# mrna_badge_v1_3.net
KiCad netlist of a schematic drawn in EAGLE
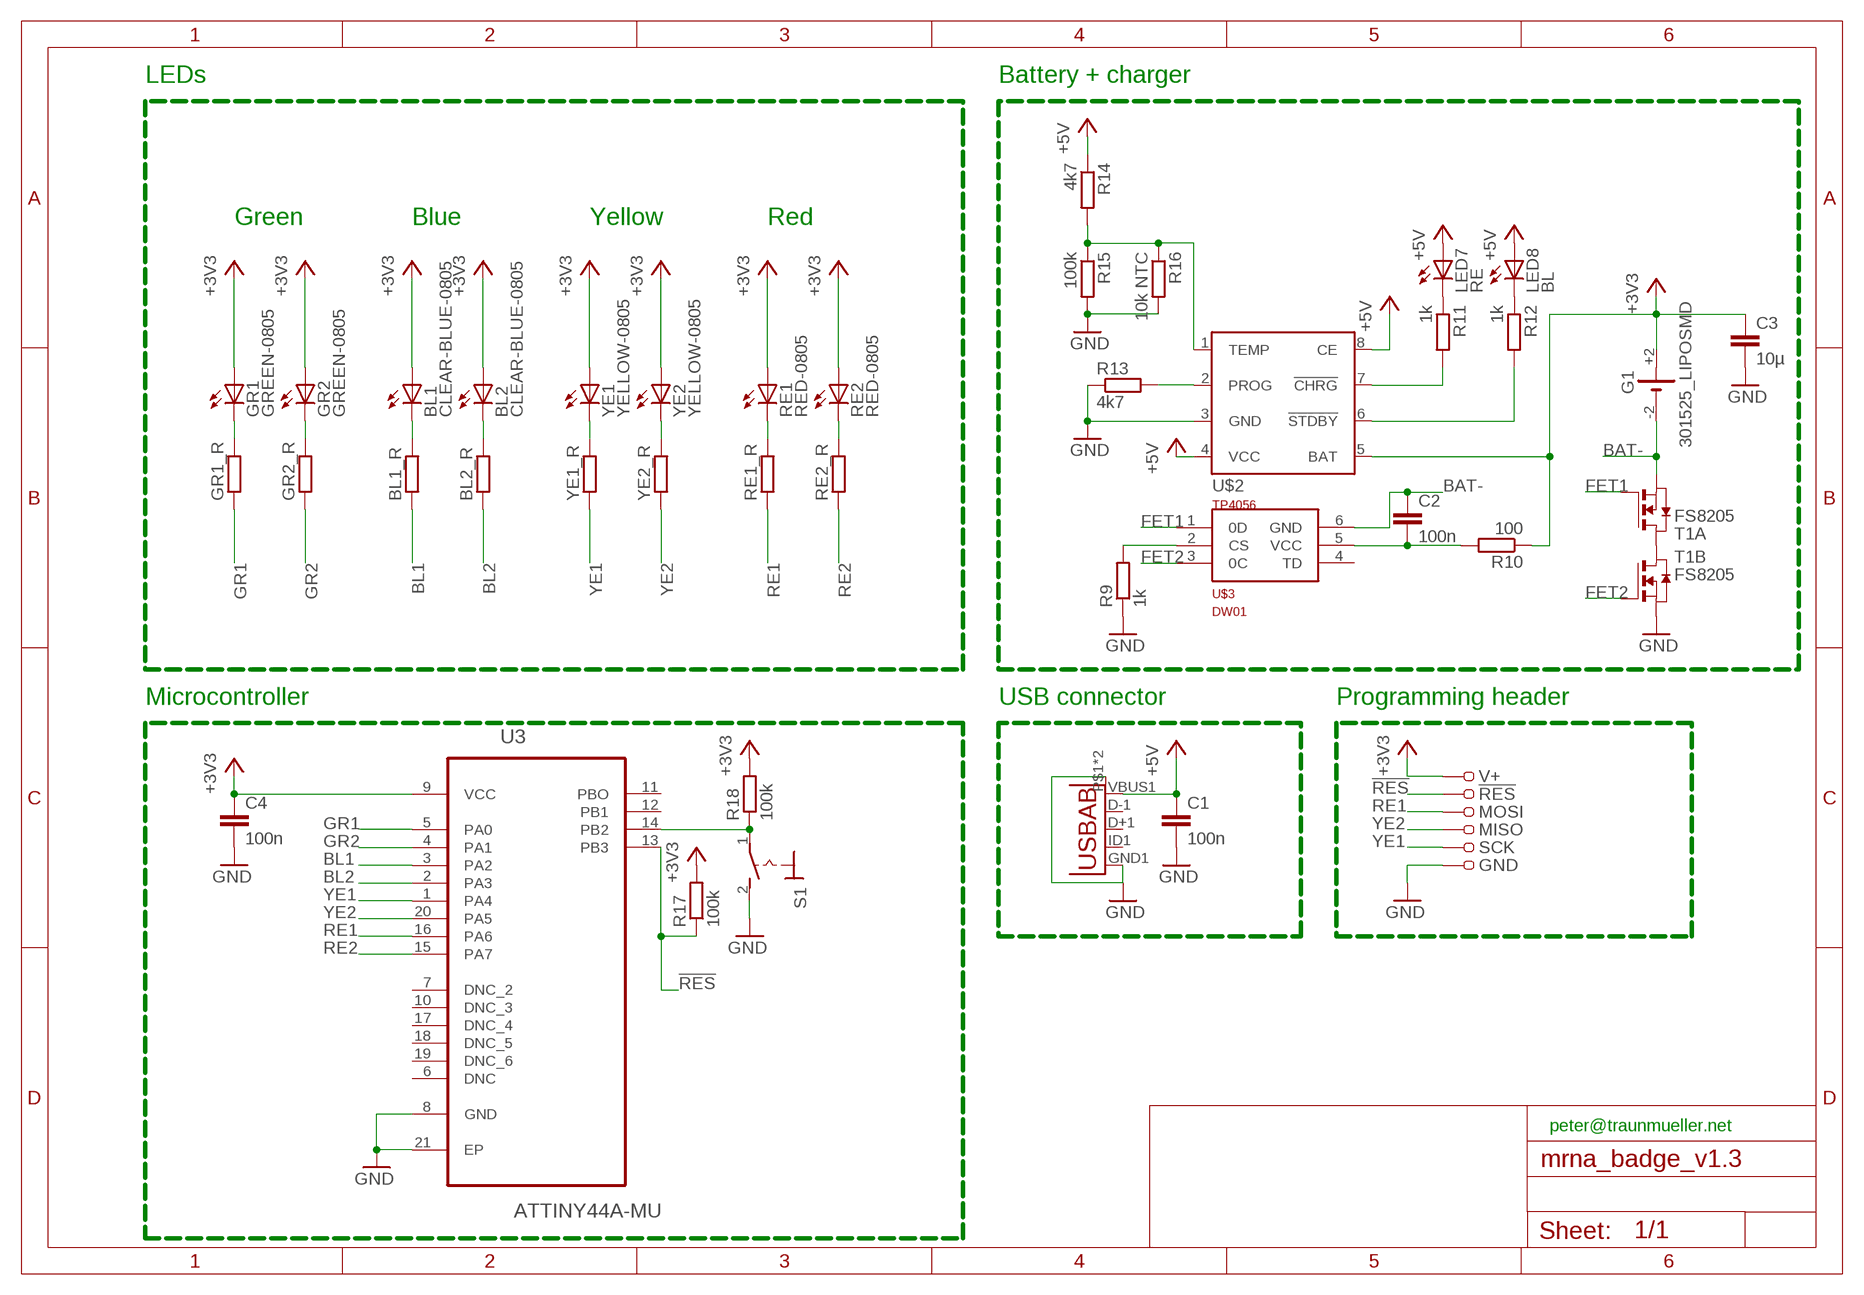
[diagram p0: schematic, sheet 1]

(export (version "E")
  (design (tool "Eeschema 10.0.6"))
  (components
    (comp (ref "!RES")
      (value "0.7MM_POGO-PINSPADS")
      (footprint "eagle-import:0.7MM_SMD_PADS")
      (libsource (lib "eagle-import") (part "0.7MM_POGO-PINSPADS"))
    )
    (comp (ref "BL1")
      (value "CLEAR-BLUE-0805")
      (footprint "eagle-import:CHIPLED_0805")
      (libsource (lib "eagle-import") (part "LEDCHIPLED_0805"))
    )
    (comp (ref "BL1_R")
      (value "R-EU_R0402")
      (footprint "eagle-import:R0402")
      (libsource (lib "eagle-import") (part "R-EU_R0402"))
    )
    (comp (ref "BL2")
      (value "CLEAR-BLUE-0805")
      (footprint "eagle-import:CHIPLED_0805")
      (libsource (lib "eagle-import") (part "LEDCHIPLED_0805"))
    )
    (comp (ref "BL2_R")
      (value "R-EU_R0402")
      (footprint "eagle-import:R0402")
      (libsource (lib "eagle-import") (part "R-EU_R0402"))
    )
    (comp (ref "C1")
      (value "100n")
      (footprint "eagle-import:C0402K")
      (libsource (lib "eagle-import") (part "C-EUC0402K"))
    )
    (comp (ref "C2")
      (value "100n")
      (footprint "eagle-import:C0402K")
      (libsource (lib "eagle-import") (part "C-EUC0402K"))
    )
    (comp (ref "C3")
      (value "10µ")
      (footprint "eagle-import:C0805K")
      (libsource (lib "eagle-import") (part "C-EUC0805K"))
    )
    (comp (ref "C4")
      (value "100n")
      (footprint "eagle-import:C0402K")
      (libsource (lib "eagle-import") (part "C-EUC0402K"))
    )
    (comp (ref "G1")
      (value "301525_LIPOSMD")
      (footprint "eagle-import:301525_LIPO_SMDCONTACTS")
      (libsource (lib "eagle-import") (part "301525_LIPOSMD"))
    )
    (comp (ref "GND")
      (value "0.7MM_POGO-PINSPADS")
      (footprint "eagle-import:0.7MM_SMD_PADS")
      (libsource (lib "eagle-import") (part "0.7MM_POGO-PINSPADS"))
    )
    (comp (ref "GR1")
      (value "GREEN-0805")
      (footprint "eagle-import:CHIPLED_0805")
      (libsource (lib "eagle-import") (part "LEDCHIPLED_0805"))
    )
    (comp (ref "GR1_R")
      (value "R-EU_R0402")
      (footprint "eagle-import:R0402")
      (libsource (lib "eagle-import") (part "R-EU_R0402"))
    )
    (comp (ref "GR2")
      (value "GREEN-0805")
      (footprint "eagle-import:CHIPLED_0805")
      (libsource (lib "eagle-import") (part "LEDCHIPLED_0805"))
    )
    (comp (ref "GR2_R")
      (value "R-EU_R0402")
      (footprint "eagle-import:R0402")
      (libsource (lib "eagle-import") (part "R-EU_R0402"))
    )
    (comp (ref "LED7")
      (value "RE")
      (footprint "eagle-import:CHIPLED_0603")
      (libsource (lib "eagle-import") (part "LEDCHIPLED_0603"))
    )
    (comp (ref "LED8")
      (value "BL")
      (footprint "eagle-import:CHIPLED_0603")
      (libsource (lib "eagle-import") (part "LEDCHIPLED_0603"))
    )
    (comp (ref "MISO")
      (value "0.7MM_POGO-PINSPADS")
      (footprint "eagle-import:0.7MM_SMD_PADS")
      (libsource (lib "eagle-import") (part "0.7MM_POGO-PINSPADS"))
    )
    (comp (ref "MOSI")
      (value "0.7MM_POGO-PINSPADS")
      (footprint "eagle-import:0.7MM_SMD_PADS")
      (libsource (lib "eagle-import") (part "0.7MM_POGO-PINSPADS"))
    )
    (comp (ref "R9")
      (value "1k")
      (footprint "eagle-import:R0402")
      (libsource (lib "eagle-import") (part "R-EU_R0402"))
    )
    (comp (ref "R10")
      (value "100")
      (footprint "eagle-import:R0402")
      (libsource (lib "eagle-import") (part "R-EU_R0402"))
    )
    (comp (ref "R11")
      (value "1k")
      (footprint "eagle-import:R0402")
      (libsource (lib "eagle-import") (part "R-EU_R0402"))
    )
    (comp (ref "R12")
      (value "1k")
      (footprint "eagle-import:R0402")
      (libsource (lib "eagle-import") (part "R-EU_R0402"))
    )
    (comp (ref "R13")
      (value "4k7")
      (footprint "eagle-import:R0402")
      (libsource (lib "eagle-import") (part "R-EU_R0402"))
    )
    (comp (ref "R14")
      (value "4k7")
      (footprint "eagle-import:R0402")
      (libsource (lib "eagle-import") (part "R-EU_R0402"))
    )
    (comp (ref "R15")
      (value "100k")
      (footprint "eagle-import:R0402")
      (libsource (lib "eagle-import") (part "R-EU_R0402"))
    )
    (comp (ref "R16")
      (value "10k NTC")
      (footprint "eagle-import:R0805")
      (libsource (lib "eagle-import") (part "R-EU_R0805"))
    )
    (comp (ref "R17")
      (value "100k")
      (footprint "eagle-import:R0402")
      (libsource (lib "eagle-import") (part "R-EU_R0402"))
    )
    (comp (ref "R18")
      (value "100k")
      (footprint "eagle-import:R0402")
      (libsource (lib "eagle-import") (part "R-EU_R0402"))
    )
    (comp (ref "RE1")
      (value "RED-0805")
      (footprint "eagle-import:CHIPLED_0805")
      (libsource (lib "eagle-import") (part "LEDCHIPLED_0805"))
    )
    (comp (ref "RE1_R")
      (value "R-EU_R0402")
      (footprint "eagle-import:R0402")
      (libsource (lib "eagle-import") (part "R-EU_R0402"))
    )
    (comp (ref "RE2")
      (value "RED-0805")
      (footprint "eagle-import:CHIPLED_0805")
      (libsource (lib "eagle-import") (part "LEDCHIPLED_0805"))
    )
    (comp (ref "RE2_R")
      (value "R-EU_R0402")
      (footprint "eagle-import:R0402")
      (libsource (lib "eagle-import") (part "R-EU_R0402"))
    )
    (comp (ref "S1")
      (value "TS-1088NOHOLES")
      (footprint "eagle-import:TS-1088_NOHOLES")
      (libsource (lib "eagle-import") (part "TS-1088NOHOLES"))
    )
    (comp (ref "SCK")
      (value "0.7MM_POGO-PINSPADS")
      (footprint "eagle-import:0.7MM_SMD_PADS")
      (libsource (lib "eagle-import") (part "0.7MM_POGO-PINSPADS"))
    )
    (comp (ref "T1")
      (value "FS8205")
      (footprint "eagle-import:TSSOP-8")
      (libsource (lib "eagle-import") (part "DMN3024LSD"))
    )
    (comp (ref "U$2")
      (value "TP4056ESOP")
      (footprint "eagle-import:ESOP23-8")
      (libsource (lib "eagle-import") (part "TP4056ESOP"))
    )
    (comp (ref "U$3")
      (value "DW01")
      (footprint "eagle-import:SOT23-6")
      (libsource (lib "eagle-import") (part "DW01"))
    )
    (comp (ref "U2")
      (value "USB\"\"")
      (footprint "eagle-import:USB-MICRO-SMD")
      (libsource (lib "eagle-import") (part "USB{dblquote}{dblquote}"))
    )
    (comp (ref "U3")
      (value "ATTINY44A-MU")
      (footprint "eagle-import:QFN50P400X400X80-21N_FOOTPRINT")
      (libsource (lib "eagle-import") (part "ATTINY24A-MUFOOT"))
    )
    (comp (ref "V+")
      (value "0.7MM_POGO-PINSPADS")
      (footprint "eagle-import:0.7MM_SMD_PADS")
      (libsource (lib "eagle-import") (part "0.7MM_POGO-PINSPADS"))
    )
    (comp (ref "YE1")
      (value "YELLOW-0805")
      (footprint "eagle-import:CHIPLED_0805")
      (libsource (lib "eagle-import") (part "LEDCHIPLED_0805"))
    )
    (comp (ref "YE1_R")
      (value "R-EU_R0402")
      (footprint "eagle-import:R0402")
      (libsource (lib "eagle-import") (part "R-EU_R0402"))
    )
    (comp (ref "YE2")
      (value "YELLOW-0805")
      (footprint "eagle-import:CHIPLED_0805")
      (libsource (lib "eagle-import") (part "LEDCHIPLED_0805"))
    )
    (comp (ref "YE2_R")
      (value "R-EU_R0402")
      (footprint "eagle-import:R0402")
      (libsource (lib "eagle-import") (part "R-EU_R0402"))
    )
  )
  (nets
    (net (code "1") (name "+3V3") (class "Default")
      (node (ref "BL1") (pin "A") (pinfunction "A_A") (pintype "passive"))
      (node (ref "BL2") (pin "A") (pinfunction "A_A") (pintype "passive"))
      (node (ref "C3") (pin "1") (pinfunction "1_1") (pintype "passive"))
      (node (ref "C4") (pin "1") (pinfunction "1_1") (pintype "passive"))
      (node (ref "G1") (pin "+2") (pinfunction "+_+2") (pintype "passive"))
      (node (ref "GR1") (pin "A") (pinfunction "A_A") (pintype "passive"))
      (node (ref "GR2") (pin "A") (pinfunction "A_A") (pintype "passive"))
      (node (ref "R10") (pin "1") (pinfunction "1_1") (pintype "passive"))
      (node (ref "R17") (pin "2") (pinfunction "2_2") (pintype "passive"))
      (node (ref "R18") (pin "2") (pinfunction "2_2") (pintype "passive"))
      (node (ref "RE1") (pin "A") (pinfunction "A_A") (pintype "passive"))
      (node (ref "RE2") (pin "A") (pinfunction "A_A") (pintype "passive"))
      (node (ref "U$2") (pin "5") (pinfunction "BAT_5") (pintype "bidirectional"))
      (node (ref "U3") (pin "9") (pinfunction "VCC_9") (pintype "power_in"))
      (node (ref "V+") (pin "P$1") (pinfunction "1_P$1") (pintype "passive"))
      (node (ref "YE1") (pin "A") (pinfunction "A_A") (pintype "passive"))
      (node (ref "YE2") (pin "A") (pinfunction "A_A") (pintype "passive"))
    )
    (net (code "2") (name "+5V") (class "Default")
      (node (ref "C1") (pin "1") (pinfunction "1_1") (pintype "passive"))
      (node (ref "LED7") (pin "A") (pinfunction "A_A") (pintype "passive"))
      (node (ref "LED8") (pin "A") (pinfunction "A_A") (pintype "passive"))
      (node (ref "R14") (pin "1") (pinfunction "1_1") (pintype "passive"))
      (node (ref "U$2") (pin "4") (pinfunction "VCC_4") (pintype "bidirectional"))
      (node (ref "U$2") (pin "8") (pinfunction "CE_8") (pintype "bidirectional"))
      (node (ref "U2") (pin "VBUS1") (pinfunction "VBUS_VBUS1") (pintype "bidirectional"))
    )
    (net (code "3") (name "/BAT-") (class "Default")
      (node (ref "C2") (pin "1") (pinfunction "1_1") (pintype "passive"))
      (node (ref "G1") (pin "-2") (pinfunction "-_-2") (pintype "passive"))
      (node (ref "T1") (pin "2") (pinfunction "S_2") (pintype "passive"))
      (node (ref "T1") (pin "3") (pinfunction "S_3") (pintype "passive"))
      (node (ref "U$3") (pin "6") (pinfunction "GND_6") (pintype "bidirectional"))
    )
    (net (code "4") (name "/BL1") (class "Default")
      (node (ref "BL1_R") (pin "1") (pinfunction "1_1") (pintype "passive"))
      (node (ref "U3") (pin "3") (pinfunction "PA2_3") (pintype "bidirectional"))
    )
    (net (code "5") (name "/BL2") (class "Default")
      (node (ref "BL2_R") (pin "1") (pinfunction "1_1") (pintype "passive"))
      (node (ref "U3") (pin "2") (pinfunction "PA3_2") (pintype "bidirectional"))
    )
    (net (code "6") (name "/FET1") (class "Default")
      (node (ref "T1") (pin "4") (pinfunction "G_4") (pintype "passive"))
      (node (ref "U$3") (pin "1") (pinfunction "0D_1") (pintype "bidirectional"))
    )
    (net (code "7") (name "/FET2") (class "Default")
      (node (ref "T1") (pin "5") (pinfunction "G_5") (pintype "passive"))
      (node (ref "U$3") (pin "3") (pinfunction "0C_3") (pintype "bidirectional"))
    )
    (net (code "8") (name "/GR1") (class "Default")
      (node (ref "GR1_R") (pin "1") (pinfunction "1_1") (pintype "passive"))
      (node (ref "U3") (pin "5") (pinfunction "PA0_5") (pintype "bidirectional"))
    )
    (net (code "9") (name "/GR2") (class "Default")
      (node (ref "GR2_R") (pin "1") (pinfunction "1_1") (pintype "passive"))
      (node (ref "U3") (pin "4") (pinfunction "PA1_4") (pintype "bidirectional"))
    )
    (net (code "11") (name "/RE1") (class "Default")
      (node (ref "MOSI") (pin "P$1") (pinfunction "1_P$1") (pintype "passive"))
      (node (ref "RE1_R") (pin "1") (pinfunction "1_1") (pintype "passive"))
      (node (ref "U3") (pin "16") (pinfunction "PA6_16") (pintype "bidirectional"))
    )
    (net (code "12") (name "/RE2") (class "Default")
      (node (ref "RE2_R") (pin "1") (pinfunction "1_1") (pintype "passive"))
      (node (ref "U3") (pin "15") (pinfunction "PA7_15") (pintype "bidirectional"))
    )
    (net (code "13") (name "/YE1") (class "Default")
      (node (ref "SCK") (pin "P$1") (pinfunction "1_P$1") (pintype "passive"))
      (node (ref "U3") (pin "1") (pinfunction "PA4_1") (pintype "bidirectional"))
      (node (ref "YE1_R") (pin "1") (pinfunction "1_1") (pintype "passive"))
    )
    (net (code "14") (name "/YE2") (class "Default")
      (node (ref "MISO") (pin "P$1") (pinfunction "1_P$1") (pintype "passive"))
      (node (ref "U3") (pin "20") (pinfunction "PA5_20") (pintype "bidirectional"))
      (node (ref "YE2_R") (pin "1") (pinfunction "1_1") (pintype "passive"))
    )
    (net (code "15") (name "/~{RES}") (class "Default")
      (node (ref "!RES") (pin "P$1") (pinfunction "1_P$1") (pintype "passive"))
      (node (ref "R17") (pin "1") (pinfunction "1_1") (pintype "passive"))
      (node (ref "U3") (pin "13") (pinfunction "PB3_13") (pintype "bidirectional"))
    )
    (net (code "16") (name "GND") (class "Default")
      (node (ref "C1") (pin "2") (pinfunction "2_2") (pintype "passive"))
      (node (ref "C3") (pin "2") (pinfunction "2_2") (pintype "passive"))
      (node (ref "C4") (pin "2") (pinfunction "2_2") (pintype "passive"))
      (node (ref "GND") (pin "P$1") (pinfunction "1_P$1") (pintype "passive"))
      (node (ref "R13") (pin "1") (pinfunction "1_1") (pintype "passive"))
      (node (ref "R15") (pin "2") (pinfunction "2_2") (pintype "passive"))
      (node (ref "R16") (pin "2") (pinfunction "2_2") (pintype "passive"))
      (node (ref "R9") (pin "1") (pinfunction "1_1") (pintype "passive"))
      (node (ref "S1") (pin "2") (pinfunction "S_2") (pintype "passive"))
      (node (ref "T1") (pin "6") (pinfunction "S_6") (pintype "passive"))
      (node (ref "T1") (pin "7") (pinfunction "S_7") (pintype "passive"))
      (node (ref "U$2") (pin "3") (pinfunction "GND_3") (pintype "bidirectional"))
      (node (ref "U2") (pin "GND1") (pinfunction "GND_GND1") (pintype "bidirectional"))
      (node (ref "U2") (pin "P$1") (pinfunction "CASE_P$1") (pintype "bidirectional"))
      (node (ref "U2") (pin "P$2") (pinfunction "CASE_P$2") (pintype "bidirectional"))
      (node (ref "U3") (pin "21") (pinfunction "EP_21") (pintype "passive"))
      (node (ref "U3") (pin "8") (pinfunction "GND_8") (pintype "passive"))
    )
    (net (code "17") (name "Net-(BL1-PadC)") (class "Default")
      (node (ref "BL1") (pin "C") (pinfunction "C_C") (pintype "passive"))
      (node (ref "BL1_R") (pin "2") (pinfunction "2_2") (pintype "passive"))
    )
    (net (code "18") (name "Net-(BL2-PadC)") (class "Default")
      (node (ref "BL2") (pin "C") (pinfunction "C_C") (pintype "passive"))
      (node (ref "BL2_R") (pin "2") (pinfunction "2_2") (pintype "passive"))
    )
    (net (code "19") (name "Net-(GR1-PadC)") (class "Default")
      (node (ref "GR1") (pin "C") (pinfunction "C_C") (pintype "passive"))
      (node (ref "GR1_R") (pin "2") (pinfunction "2_2") (pintype "passive"))
    )
    (net (code "20") (name "Net-(GR2-PadC)") (class "Default")
      (node (ref "GR2") (pin "C") (pinfunction "C_C") (pintype "passive"))
      (node (ref "GR2_R") (pin "2") (pinfunction "2_2") (pintype "passive"))
    )
    (net (code "21") (name "Net-(LED7-PadC)") (class "Default")
      (node (ref "LED7") (pin "C") (pinfunction "C_C") (pintype "passive"))
      (node (ref "R11") (pin "1") (pinfunction "1_1") (pintype "passive"))
    )
    (net (code "22") (name "Net-(LED8-PadC)") (class "Default")
      (node (ref "LED8") (pin "C") (pinfunction "C_C") (pintype "passive"))
      (node (ref "R12") (pin "1") (pinfunction "1_1") (pintype "passive"))
    )
    (net (code "23") (name "Net-(RE1-PadC)") (class "Default")
      (node (ref "RE1") (pin "C") (pinfunction "C_C") (pintype "passive"))
      (node (ref "RE1_R") (pin "2") (pinfunction "2_2") (pintype "passive"))
    )
    (net (code "24") (name "Net-(RE2-PadC)") (class "Default")
      (node (ref "RE2") (pin "C") (pinfunction "C_C") (pintype "passive"))
      (node (ref "RE2_R") (pin "2") (pinfunction "2_2") (pintype "passive"))
    )
    (net (code "25") (name "Net-(S1-P)") (class "Default")
      (node (ref "R18") (pin "1") (pinfunction "1_1") (pintype "passive"))
      (node (ref "S1") (pin "1") (pinfunction "P_1") (pintype "passive"))
      (node (ref "U3") (pin "14") (pinfunction "PB2_14") (pintype "bidirectional"))
    )
    (net (code "26") (name "Net-(T1A-D)") (class "Default")
      (node (ref "T1") (pin "1") (pinfunction "D_1") (pintype "passive"))
      (node (ref "T1") (pin "8") (pinfunction "D_8") (pintype "passive"))
    )
    (net (code "27") (name "Net-(U$2-PROG)") (class "Default")
      (node (ref "R13") (pin "2") (pinfunction "2_2") (pintype "passive"))
      (node (ref "U$2") (pin "2") (pinfunction "PROG_2") (pintype "bidirectional"))
    )
    (net (code "28") (name "Net-(U$2-TEMP)") (class "Default")
      (node (ref "R14") (pin "2") (pinfunction "2_2") (pintype "passive"))
      (node (ref "R15") (pin "1") (pinfunction "1_1") (pintype "passive"))
      (node (ref "R16") (pin "1") (pinfunction "1_1") (pintype "passive"))
      (node (ref "U$2") (pin "1") (pinfunction "TEMP_1") (pintype "bidirectional"))
    )
    (net (code "29") (name "Net-(U$2-~{CHRG})") (class "Default")
      (node (ref "R11") (pin "2") (pinfunction "2_2") (pintype "passive"))
      (node (ref "U$2") (pin "7") (pinfunction "~{CHRG}_7") (pintype "bidirectional"))
    )
    (net (code "30") (name "Net-(U$2-~{STDBY})") (class "Default")
      (node (ref "R12") (pin "2") (pinfunction "2_2") (pintype "passive"))
      (node (ref "U$2") (pin "6") (pinfunction "~{STDBY}_6") (pintype "bidirectional"))
    )
    (net (code "31") (name "Net-(U$3-CS)") (class "Default")
      (node (ref "R9") (pin "2") (pinfunction "2_2") (pintype "passive"))
      (node (ref "U$3") (pin "2") (pinfunction "CS_2") (pintype "bidirectional"))
    )
    (net (code "32") (name "Net-(U$3-VCC)") (class "Default")
      (node (ref "C2") (pin "2") (pinfunction "2_2") (pintype "passive"))
      (node (ref "R10") (pin "2") (pinfunction "2_2") (pintype "passive"))
      (node (ref "U$3") (pin "5") (pinfunction "VCC_5") (pintype "bidirectional"))
    )
    (net (code "33") (name "Net-(YE1-PadC)") (class "Default")
      (node (ref "YE1") (pin "C") (pinfunction "C_C") (pintype "passive"))
      (node (ref "YE1_R") (pin "2") (pinfunction "2_2") (pintype "passive"))
    )
    (net (code "34") (name "Net-(YE2-PadC)") (class "Default")
      (node (ref "YE2") (pin "C") (pinfunction "C_C") (pintype "passive"))
      (node (ref "YE2_R") (pin "2") (pinfunction "2_2") (pintype "passive"))
    )
    (net (code "35") (name "unconnected-(U$3-TD-Pad4)") (class "Default")
      (node (ref "U$3") (pin "4") (pinfunction "TD_4") (pintype "bidirectional"))
    )
    (net (code "36") (name "unconnected-(U2-D+-PadD+1)") (class "Default")
      (node (ref "U2") (pin "D+1") (pinfunction "D+_D+1") (pintype "bidirectional"))
    )
    (net (code "37") (name "unconnected-(U2-D--PadD-1)") (class "Default")
      (node (ref "U2") (pin "D-1") (pinfunction "D-_D-1") (pintype "bidirectional"))
    )
    (net (code "38") (name "unconnected-(U2-USBID-PadID1)") (class "Default")
      (node (ref "U2") (pin "ID1") (pinfunction "USBID_ID1") (pintype "bidirectional"))
    )
    (net (code "39") (name "unconnected-(U3-DNC-Pad6)") (class "Default")
      (node (ref "U3") (pin "6") (pinfunction "DNC_6") (pintype "no_connect"))
    )
    (net (code "40") (name "unconnected-(U3-DNC_2-Pad7)") (class "Default")
      (node (ref "U3") (pin "7") (pinfunction "DNC_2_7") (pintype "no_connect"))
    )
    (net (code "41") (name "unconnected-(U3-DNC_3-Pad10)") (class "Default")
      (node (ref "U3") (pin "10") (pinfunction "DNC_3_10") (pintype "no_connect"))
    )
    (net (code "42") (name "unconnected-(U3-DNC_4-Pad17)") (class "Default")
      (node (ref "U3") (pin "17") (pinfunction "DNC_4_17") (pintype "no_connect"))
    )
    (net (code "43") (name "unconnected-(U3-DNC_5-Pad18)") (class "Default")
      (node (ref "U3") (pin "18") (pinfunction "DNC_5_18") (pintype "no_connect"))
    )
    (net (code "44") (name "unconnected-(U3-DNC_6-Pad19)") (class "Default")
      (node (ref "U3") (pin "19") (pinfunction "DNC_6_19") (pintype "no_connect"))
    )
    (net (code "45") (name "unconnected-(U3-PB1-Pad12)") (class "Default")
      (node (ref "U3") (pin "12") (pinfunction "PB1_12") (pintype "bidirectional"))
    )
    (net (code "46") (name "unconnected-(U3-PBO-Pad11)") (class "Default")
      (node (ref "U3") (pin "11") (pinfunction "PBO_11") (pintype "bidirectional"))
    )
  )
)
